# power_supply_switching.net
KiCad netlist of a schematic drawn in Altium Designer
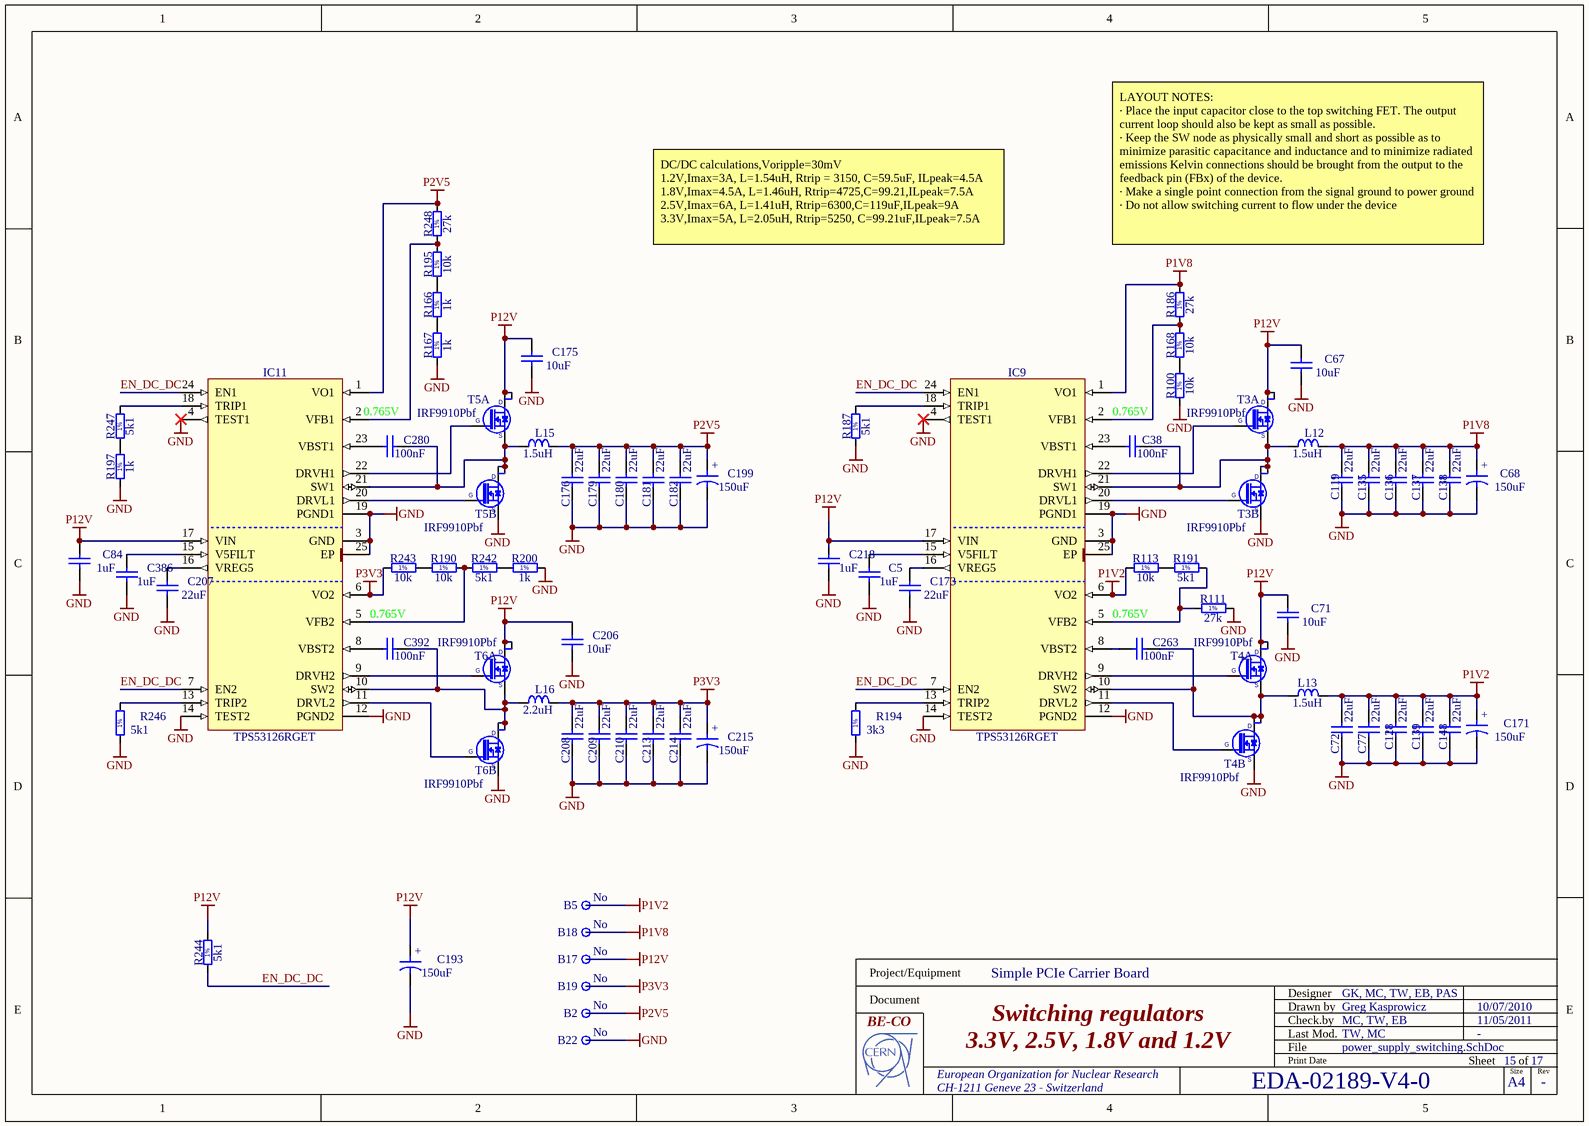
[diagram p0: power_supply_switching.SchDoc]

(export (version "E")
  (design (tool "Eeschema 10.0.6"))
  (components
    (comp (ref "B2")
      (value "Test Point")
      (footprint "VERO_20-2136")
      (description "Single Terminal Socket")
      (fields
        (field (name "PART NUMBER") "VERO_20-2136")
        (field (name "MOUNTED") "No")
        (field (name "MANUFACTURER") "VERO TECHNOLOGIES")
        (field (name "AUTHOR") "CERN DEM JLC")
      )
      (libsource (lib "Connectors") (part "Single Terminal Socket"))
    )
    (comp (ref "B5")
      (value "Test Point")
      (footprint "VERO_20-2136")
      (description "Single Terminal Socket")
      (fields
        (field (name "PART NUMBER") "VERO_20-2136")
        (field (name "MOUNTED") "No")
        (field (name "MANUFACTURER") "VERO TECHNOLOGIES")
        (field (name "AUTHOR") "CERN DEM JLC")
      )
      (libsource (lib "Connectors") (part "Single Terminal Socket"))
    )
    (comp (ref "B17")
      (value "Test Point")
      (footprint "VERO_20-2136")
      (description "Single Terminal Socket")
      (fields
        (field (name "PART NUMBER") "VERO_20-2136")
        (field (name "MOUNTED") "No")
        (field (name "MANUFACTURER") "VERO TECHNOLOGIES")
        (field (name "AUTHOR") "CERN DEM JLC")
      )
      (libsource (lib "Connectors") (part "Single Terminal Socket"))
    )
    (comp (ref "B18")
      (value "Test Point")
      (footprint "VERO_20-2136")
      (description "Single Terminal Socket")
      (fields
        (field (name "PART NUMBER") "VERO_20-2136")
        (field (name "MOUNTED") "No")
        (field (name "MANUFACTURER") "VERO TECHNOLOGIES")
        (field (name "AUTHOR") "CERN DEM JLC")
      )
      (libsource (lib "Connectors") (part "Single Terminal Socket"))
    )
    (comp (ref "B19")
      (value "Test Point")
      (footprint "VERO_20-2136")
      (description "Single Terminal Socket")
      (fields
        (field (name "PART NUMBER") "VERO_20-2136")
        (field (name "MOUNTED") "No")
        (field (name "MANUFACTURER") "VERO TECHNOLOGIES")
        (field (name "AUTHOR") "CERN DEM JLC")
      )
      (libsource (lib "Connectors") (part "Single Terminal Socket"))
    )
    (comp (ref "B22")
      (value "Test Point")
      (footprint "VERO_20-2136")
      (description "Single Terminal Socket")
      (fields
        (field (name "PART NUMBER") "VERO_20-2136")
        (field (name "MOUNTED") "No")
        (field (name "MANUFACTURER") "VERO TECHNOLOGIES")
        (field (name "AUTHOR") "CERN DEM JLC")
      )
      (libsource (lib "Connectors") (part "Single Terminal Socket"))
    )
    (comp (ref "C5")
      (value "1uF")
      (footprint "CAPC1608X87N")
      (description "Non-polarised capacitor")
      (fields
        (field (name "PART NUMBER") "CC0603_1UF_16V_10%_X7R")
        (field (name "VOLTAGE") "16V")
        (field (name "AUTHOR") "CERN DEM JLC")
      )
      (libsource (lib "Capacitors") (part "Capacitor - non polarized"))
    )
    (comp (ref "C38")
      (value "100nF")
      (footprint "CAPC1608X87N")
      (description "Non-polarised capacitor")
      (fields
        (field (name "PART NUMBER") "CC0603_100NF_50V_10%_X7R")
        (field (name "VOLTAGE") "50V")
        (field (name "AUTHOR") "CERN DEM JLC")
      )
      (libsource (lib "Capacitors") (part "Capacitor - non polarized"))
    )
    (comp (ref "C67")
      (value "10uF")
      (footprint "CAPC3225X270N")
      (description "Non-polarised capacitor")
      (fields
        (field (name "PART NUMBER") "CC1210_10UF_25V_10%_X7R")
        (field (name "VOLTAGE") "25V")
        (field (name "AUTHOR") "CERN DEM JLC")
      )
      (libsource (lib "Capacitors") (part "Capacitor - non polarized"))
    )
    (comp (ref "C68")
      (value "150uF")
      (footprint "CAPPR350-850X700")
      (description "Polarised capacitor")
      (fields
        (field (name "PART NUMBER") "CAER_150UF_6.3V_20%_SANYO_6SEQP150M")
        (field (name "VOLTAGE") "6.3V")
        (field (name "AUTHOR") "CERN DEM JLC")
      )
      (libsource (lib "Capacitors") (part "Capacitor - polarized"))
    )
    (comp (ref "C71")
      (value "10uF")
      (footprint "CAPC3225X270N")
      (description "Non-polarised capacitor")
      (fields
        (field (name "PART NUMBER") "CC1210_10UF_25V_10%_X7R")
        (field (name "VOLTAGE") "25V")
        (field (name "AUTHOR") "CERN DEM JLC")
      )
      (libsource (lib "Capacitors") (part "Capacitor - non polarized"))
    )
    (comp (ref "C72")
      (value "22uF")
      (footprint "CAPC3216X180N")
      (description "Non-polarised capacitor")
      (fields
        (field (name "PART NUMBER") "CC1206_22UF_10V_10%_X7R")
        (field (name "VOLTAGE") "10V")
        (field (name "AUTHOR") "CERN DEM JLC")
      )
      (libsource (lib "Capacitors") (part "Capacitor - non polarized"))
    )
    (comp (ref "C77")
      (value "22uF")
      (footprint "CAPC3216X180N")
      (description "Non-polarised capacitor")
      (fields
        (field (name "PART NUMBER") "CC1206_22UF_10V_10%_X7R")
        (field (name "VOLTAGE") "10V")
        (field (name "AUTHOR") "CERN DEM JLC")
      )
      (libsource (lib "Capacitors") (part "Capacitor - non polarized"))
    )
    (comp (ref "C84")
      (value "1uF")
      (footprint "CAPC1608X87N")
      (description "Non-polarised capacitor")
      (fields
        (field (name "PART NUMBER") "CC0603_1UF_16V_10%_X7R")
        (field (name "VOLTAGE") "16V")
        (field (name "AUTHOR") "CERN DEM JLC")
      )
      (libsource (lib "Capacitors") (part "Capacitor - non polarized"))
    )
    (comp (ref "C119")
      (value "22uF")
      (footprint "CAPC3216X180N")
      (description "Non-polarised capacitor")
      (fields
        (field (name "PART NUMBER") "CC1206_22UF_10V_10%_X7R")
        (field (name "VOLTAGE") "10V")
        (field (name "AUTHOR") "CERN DEM JLC")
      )
      (libsource (lib "Capacitors") (part "Capacitor - non polarized"))
    )
    (comp (ref "C128")
      (value "22uF")
      (footprint "CAPC3216X180N")
      (description "Non-polarised capacitor")
      (fields
        (field (name "PART NUMBER") "CC1206_22UF_10V_10%_X7R")
        (field (name "VOLTAGE") "10V")
        (field (name "AUTHOR") "CERN DEM JLC")
      )
      (libsource (lib "Capacitors") (part "Capacitor - non polarized"))
    )
    (comp (ref "C135")
      (value "22uF")
      (footprint "CAPC3216X180N")
      (description "Non-polarised capacitor")
      (fields
        (field (name "PART NUMBER") "CC1206_22UF_10V_10%_X7R")
        (field (name "VOLTAGE") "10V")
        (field (name "AUTHOR") "CERN DEM JLC")
      )
      (libsource (lib "Capacitors") (part "Capacitor - non polarized"))
    )
    (comp (ref "C136")
      (value "22uF")
      (footprint "CAPC3216X180N")
      (description "Non-polarised capacitor")
      (fields
        (field (name "PART NUMBER") "CC1206_22UF_10V_10%_X7R")
        (field (name "VOLTAGE") "10V")
        (field (name "AUTHOR") "CERN DEM JLC")
      )
      (libsource (lib "Capacitors") (part "Capacitor - non polarized"))
    )
    (comp (ref "C137")
      (value "22uF")
      (footprint "CAPC3216X180N")
      (description "Non-polarised capacitor")
      (fields
        (field (name "PART NUMBER") "CC1206_22UF_10V_10%_X7R")
        (field (name "VOLTAGE") "10V")
        (field (name "AUTHOR") "CERN DEM JLC")
      )
      (libsource (lib "Capacitors") (part "Capacitor - non polarized"))
    )
    (comp (ref "C138")
      (value "22uF")
      (footprint "CAPC3216X180N")
      (description "Non-polarised capacitor")
      (fields
        (field (name "PART NUMBER") "CC1206_22UF_10V_10%_X7R")
        (field (name "VOLTAGE") "10V")
        (field (name "AUTHOR") "CERN DEM JLC")
      )
      (libsource (lib "Capacitors") (part "Capacitor - non polarized"))
    )
    (comp (ref "C139")
      (value "22uF")
      (footprint "CAPC3216X180N")
      (description "Non-polarised capacitor")
      (fields
        (field (name "PART NUMBER") "CC1206_22UF_10V_10%_X7R")
        (field (name "VOLTAGE") "10V")
        (field (name "AUTHOR") "CERN DEM JLC")
      )
      (libsource (lib "Capacitors") (part "Capacitor - non polarized"))
    )
    (comp (ref "C148")
      (value "22uF")
      (footprint "CAPC3216X180N")
      (description "Non-polarised capacitor")
      (fields
        (field (name "PART NUMBER") "CC1206_22UF_10V_10%_X7R")
        (field (name "VOLTAGE") "10V")
        (field (name "AUTHOR") "CERN DEM JLC")
      )
      (libsource (lib "Capacitors") (part "Capacitor - non polarized"))
    )
    (comp (ref "C171")
      (value "150uF")
      (footprint "CAPPR350-850X700")
      (description "Polarised capacitor")
      (fields
        (field (name "PART NUMBER") "CAER_150UF_6.3V_20%_SANYO_6SEQP150M")
        (field (name "VOLTAGE") "6.3V")
        (field (name "AUTHOR") "CERN DEM JLC")
      )
      (libsource (lib "Capacitors") (part "Capacitor - polarized"))
    )
    (comp (ref "C173")
      (value "22uF")
      (footprint "CAPC3216X180N")
      (description "Non-polarised capacitor")
      (fields
        (field (name "PART NUMBER") "CC1206_22UF_10V_10%_X7R")
        (field (name "VOLTAGE") "10V")
        (field (name "AUTHOR") "CERN DEM JLC")
      )
      (libsource (lib "Capacitors") (part "Capacitor - non polarized"))
    )
    (comp (ref "C175")
      (value "10uF")
      (footprint "CAPC3225X270N")
      (description "Non-polarised capacitor")
      (fields
        (field (name "PART NUMBER") "CC1210_10UF_25V_10%_X7R")
        (field (name "VOLTAGE") "25V")
        (field (name "AUTHOR") "CERN DEM JLC")
      )
      (libsource (lib "Capacitors") (part "Capacitor - non polarized"))
    )
    (comp (ref "C176")
      (value "22uF")
      (footprint "CAPC3216X180N")
      (description "Non-polarised capacitor")
      (fields
        (field (name "PART NUMBER") "CC1206_22UF_10V_10%_X7R")
        (field (name "VOLTAGE") "10V")
        (field (name "AUTHOR") "CERN DEM JLC")
      )
      (libsource (lib "Capacitors") (part "Capacitor - non polarized"))
    )
    (comp (ref "C179")
      (value "22uF")
      (footprint "CAPC3216X180N")
      (description "Non-polarised capacitor")
      (fields
        (field (name "PART NUMBER") "CC1206_22UF_10V_10%_X7R")
        (field (name "VOLTAGE") "10V")
        (field (name "AUTHOR") "CERN DEM JLC")
      )
      (libsource (lib "Capacitors") (part "Capacitor - non polarized"))
    )
    (comp (ref "C180")
      (value "22uF")
      (footprint "CAPC3216X180N")
      (description "Non-polarised capacitor")
      (fields
        (field (name "PART NUMBER") "CC1206_22UF_10V_10%_X7R")
        (field (name "VOLTAGE") "10V")
        (field (name "AUTHOR") "CERN DEM JLC")
      )
      (libsource (lib "Capacitors") (part "Capacitor - non polarized"))
    )
    (comp (ref "C181")
      (value "22uF")
      (footprint "CAPC3216X180N")
      (description "Non-polarised capacitor")
      (fields
        (field (name "PART NUMBER") "CC1206_22UF_10V_10%_X7R")
        (field (name "VOLTAGE") "10V")
        (field (name "AUTHOR") "CERN DEM JLC")
      )
      (libsource (lib "Capacitors") (part "Capacitor - non polarized"))
    )
    (comp (ref "C182")
      (value "22uF")
      (footprint "CAPC3216X180N")
      (description "Non-polarised capacitor")
      (fields
        (field (name "PART NUMBER") "CC1206_22UF_10V_10%_X7R")
        (field (name "VOLTAGE") "10V")
        (field (name "AUTHOR") "CERN DEM JLC")
      )
      (libsource (lib "Capacitors") (part "Capacitor - non polarized"))
    )
    (comp (ref "C193")
      (value "150uF")
      (footprint "CAPPR500-1050X800")
      (description "Polarised capacitor")
      (fields
        (field (name "PART NUMBER") "CAER_150UF_16V_20%_SANYO_16SEQP150M")
        (field (name "VOLTAGE") "16V")
        (field (name "AUTHOR") "CERN DEM JLC")
      )
      (libsource (lib "Capacitors") (part "Capacitor - polarized"))
    )
    (comp (ref "C199")
      (value "150uF")
      (footprint "CAPPR350-850X700")
      (description "Polarised capacitor")
      (fields
        (field (name "PART NUMBER") "CAER_150UF_6.3V_20%_SANYO_6SEQP150M")
        (field (name "VOLTAGE") "6.3V")
        (field (name "AUTHOR") "CERN DEM JLC")
      )
      (libsource (lib "Capacitors") (part "Capacitor - polarized"))
    )
    (comp (ref "C206")
      (value "10uF")
      (footprint "CAPC3225X270N")
      (description "Non-polarised capacitor")
      (fields
        (field (name "PART NUMBER") "CC1210_10UF_25V_10%_X7R")
        (field (name "VOLTAGE") "25V")
        (field (name "AUTHOR") "CERN DEM JLC")
      )
      (libsource (lib "Capacitors") (part "Capacitor - non polarized"))
    )
    (comp (ref "C207")
      (value "22uF")
      (footprint "CAPC3216X180N")
      (description "Non-polarised capacitor")
      (fields
        (field (name "PART NUMBER") "CC1206_22UF_10V_10%_X7R")
        (field (name "VOLTAGE") "10V")
        (field (name "AUTHOR") "CERN DEM JLC")
      )
      (libsource (lib "Capacitors") (part "Capacitor - non polarized"))
    )
    (comp (ref "C208")
      (value "22uF")
      (footprint "CAPC3216X180N")
      (description "Non-polarised capacitor")
      (fields
        (field (name "PART NUMBER") "CC1206_22UF_10V_10%_X7R")
        (field (name "VOLTAGE") "10V")
        (field (name "AUTHOR") "CERN DEM JLC")
      )
      (libsource (lib "Capacitors") (part "Capacitor - non polarized"))
    )
    (comp (ref "C209")
      (value "22uF")
      (footprint "CAPC3216X180N")
      (description "Non-polarised capacitor")
      (fields
        (field (name "PART NUMBER") "CC1206_22UF_10V_10%_X7R")
        (field (name "VOLTAGE") "10V")
        (field (name "AUTHOR") "CERN DEM JLC")
      )
      (libsource (lib "Capacitors") (part "Capacitor - non polarized"))
    )
    (comp (ref "C210")
      (value "22uF")
      (footprint "CAPC3216X180N")
      (description "Non-polarised capacitor")
      (fields
        (field (name "PART NUMBER") "CC1206_22UF_10V_10%_X7R")
        (field (name "VOLTAGE") "10V")
        (field (name "AUTHOR") "CERN DEM JLC")
      )
      (libsource (lib "Capacitors") (part "Capacitor - non polarized"))
    )
    (comp (ref "C213")
      (value "22uF")
      (footprint "CAPC3216X180N")
      (description "Non-polarised capacitor")
      (fields
        (field (name "PART NUMBER") "CC1206_22UF_10V_10%_X7R")
        (field (name "VOLTAGE") "10V")
        (field (name "AUTHOR") "CERN DEM JLC")
      )
      (libsource (lib "Capacitors") (part "Capacitor - non polarized"))
    )
    (comp (ref "C214")
      (value "22uF")
      (footprint "CAPC3216X180N")
      (description "Non-polarised capacitor")
      (fields
        (field (name "PART NUMBER") "CC1206_22UF_10V_10%_X7R")
        (field (name "VOLTAGE") "10V")
        (field (name "AUTHOR") "CERN DEM JLC")
      )
      (libsource (lib "Capacitors") (part "Capacitor - non polarized"))
    )
    (comp (ref "C215")
      (value "150uF")
      (footprint "CAPPR350-850X700")
      (description "Polarised capacitor")
      (fields
        (field (name "PART NUMBER") "CAER_150UF_6.3V_20%_SANYO_6SEQP150M")
        (field (name "VOLTAGE") "6.3V")
        (field (name "AUTHOR") "CERN DEM JLC")
      )
      (libsource (lib "Capacitors") (part "Capacitor - polarized"))
    )
    (comp (ref "C218")
      (value "1uF")
      (footprint "CAPC1608X87N")
      (description "Non-polarised capacitor")
      (fields
        (field (name "PART NUMBER") "CC0603_1UF_16V_10%_X7R")
        (field (name "VOLTAGE") "16V")
        (field (name "AUTHOR") "CERN DEM JLC")
      )
      (libsource (lib "Capacitors") (part "Capacitor - non polarized"))
    )
    (comp (ref "C263")
      (value "100nF")
      (footprint "CAPC1608X87N")
      (description "Non-polarised capacitor")
      (fields
        (field (name "PART NUMBER") "CC0603_100NF_50V_10%_X7R")
        (field (name "VOLTAGE") "50V")
        (field (name "AUTHOR") "CERN DEM JLC")
      )
      (libsource (lib "Capacitors") (part "Capacitor - non polarized"))
    )
    (comp (ref "C280")
      (value "100nF")
      (footprint "CAPC1608X87N")
      (description "Non-polarised capacitor")
      (fields
        (field (name "PART NUMBER") "CC0603_100NF_50V_10%_X7R")
        (field (name "VOLTAGE") "50V")
        (field (name "AUTHOR") "CERN DEM JLC")
      )
      (libsource (lib "Capacitors") (part "Capacitor - non polarized"))
    )
    (comp (ref "C386")
      (value "1uF")
      (footprint "CAPC1608X87N")
      (description "Non-polarised capacitor")
      (fields
        (field (name "PART NUMBER") "CC0603_1UF_16V_10%_X7R")
        (field (name "VOLTAGE") "16V")
        (field (name "AUTHOR") "CERN DEM JLC")
      )
      (libsource (lib "Capacitors") (part "Capacitor - non polarized"))
    )
    (comp (ref "C392")
      (value "100nF")
      (footprint "CAPC1608X87N")
      (description "Non-polarised capacitor")
      (fields
        (field (name "PART NUMBER") "CC0603_100NF_50V_10%_X7R")
        (field (name "VOLTAGE") "50V")
        (field (name "AUTHOR") "CERN DEM JLC")
      )
      (libsource (lib "Capacitors") (part "Capacitor - non polarized"))
    )
    (comp (ref "IC9")
      (value "TPS53126RGET")
      (footprint "QFN50P400X400X100-25N-S255")
      (description "Dual Synchronous Step-Down Controller For Low Voltage Power Rails")
      (fields (field (name "MANUFACTURER") "TEXAS INSTRUMENTS") (field (name "AUTHOR") "CERN DEM JLC"))
      (libsource (lib "ICs And Semiconductors") (part "TPS53126RGET"))
    )
    (comp (ref "IC11")
      (value "TPS53126RGET")
      (footprint "QFN50P400X400X100-25N-S255")
      (description "Dual Synchronous Step-Down Controller For Low Voltage Power Rails")
      (fields (field (name "MANUFACTURER") "TEXAS INSTRUMENTS") (field (name "AUTHOR") "CERN DEM JLC"))
      (libsource (lib "ICs And Semiconductors") (part "TPS53126RGET"))
    )
    (comp (ref "L12")
      (value "1.5uH")
      (footprint "IND_BOURNS_SRR1260")
      (description "Inductor")
      (fields
        (field (name "PART NUMBER") "IND_1.5UH_30%_BOURNS_SRR1260")
        (field (name "POWER") "8.8A")
        (field (name "AUTHOR") "CERN DEM JLC")
      )
      (libsource (lib "Inductors & Transformers") (part "Inductor"))
    )
    (comp (ref "L13")
      (value "1.5uH")
      (footprint "IND_BOURNS_SRR1260")
      (description "Inductor")
      (fields
        (field (name "PART NUMBER") "IND_1.5UH_30%_BOURNS_SRR1260")
        (field (name "POWER") "8.8A")
        (field (name "AUTHOR") "CERN DEM JLC")
      )
      (libsource (lib "Inductors & Transformers") (part "Inductor"))
    )
    (comp (ref "L15")
      (value "1.5uH")
      (footprint "IND_BOURNS_SRR1260")
      (description "Inductor")
      (fields
        (field (name "PART NUMBER") "IND_1.5UH_30%_BOURNS_SRR1260")
        (field (name "POWER") "8.8A")
        (field (name "AUTHOR") "CERN DEM JLC")
      )
      (libsource (lib "Inductors & Transformers") (part "Inductor"))
    )
    (comp (ref "L16")
      (value "2.2uH")
      (footprint "IND_BOURNS_SRR1260")
      (description "Inductor")
      (fields
        (field (name "PART NUMBER") "IND_2.2UH_30%_BOURNS_SRR1260")
        (field (name "POWER") "8.2A")
        (field (name "AUTHOR") "CERN DEM JLC")
      )
      (libsource (lib "Inductors & Transformers") (part "Inductor"))
    )
    (comp (ref "R100")
      (value "10k")
      (footprint "RESC1608X55N")
      (description "Resistor - 1%")
      (fields
        (field (name "PART NUMBER") "R0603_10K_1%_0.1W_100PPM")
        (field (name "POWER") "0.1W")
        (field (name "AUTHOR") "CERN DEM JLC")
      )
      (libsource (lib "Resistors") (part "Resistor - 1%"))
    )
    (comp (ref "R111")
      (value "27k")
      (footprint "RESC1608X55N")
      (description "Resistor - 1%")
      (fields
        (field (name "PART NUMBER") "R0603_27K_1%_0.1W_100PPM")
        (field (name "POWER") "0.1W")
        (field (name "AUTHOR") "CERN DEM JLC")
      )
      (libsource (lib "Resistors") (part "Resistor - 1%"))
    )
    (comp (ref "R113")
      (value "10k")
      (footprint "RESC1608X55N")
      (description "Resistor - 1%")
      (fields
        (field (name "PART NUMBER") "R0603_10K_1%_0.1W_100PPM")
        (field (name "POWER") "0.1W")
        (field (name "AUTHOR") "CERN DEM JLC")
      )
      (libsource (lib "Resistors") (part "Resistor - 1%"))
    )
    (comp (ref "R166")
      (value "1k")
      (footprint "RESC1608X55N")
      (description "Resistor - 1%")
      (fields
        (field (name "PART NUMBER") "R0603_1K_1%_0.1W_100PPM")
        (field (name "POWER") "0.1W")
        (field (name "AUTHOR") "CERN DEM JLC")
      )
      (libsource (lib "Resistors") (part "Resistor - 1%"))
    )
    (comp (ref "R167")
      (value "1k")
      (footprint "RESC1608X55N")
      (description "Resistor - 1%")
      (fields
        (field (name "PART NUMBER") "R0603_1K_1%_0.1W_100PPM")
        (field (name "POWER") "0.1W")
        (field (name "AUTHOR") "CERN DEM JLC")
      )
      (libsource (lib "Resistors") (part "Resistor - 1%"))
    )
    (comp (ref "R168")
      (value "10k")
      (footprint "RESC1608X55N")
      (description "Resistor - 1%")
      (fields
        (field (name "PART NUMBER") "R0603_10K_1%_0.1W_100PPM")
        (field (name "POWER") "0.1W")
        (field (name "AUTHOR") "CERN DEM JLC")
      )
      (libsource (lib "Resistors") (part "Resistor - 1%"))
    )
    (comp (ref "R186")
      (value "27k")
      (footprint "RESC1608X55N")
      (description "Resistor - 1%")
      (fields
        (field (name "PART NUMBER") "R0603_27K_1%_0.1W_100PPM")
        (field (name "POWER") "0.1W")
        (field (name "AUTHOR") "CERN DEM JLC")
      )
      (libsource (lib "Resistors") (part "Resistor - 1%"))
    )
    (comp (ref "R187")
      (value "5k1")
      (footprint "RESC1608X55N")
      (description "Resistor - 1%")
      (fields
        (field (name "PART NUMBER") "R0603_5K1_1%_0.1W_100PPM")
        (field (name "POWER") "0.1W")
        (field (name "AUTHOR") "CERN DEM JLC")
      )
      (libsource (lib "Resistors") (part "Resistor - 1%"))
    )
    (comp (ref "R190")
      (value "10k")
      (footprint "RESC1608X55N")
      (description "Resistor - 1%")
      (fields
        (field (name "PART NUMBER") "R0603_10K_1%_0.1W_100PPM")
        (field (name "POWER") "0.1W")
        (field (name "AUTHOR") "CERN DEM JLC")
      )
      (libsource (lib "Resistors") (part "Resistor - 1%"))
    )
    (comp (ref "R191")
      (value "5k1")
      (footprint "RESC1608X55N")
      (description "Resistor - 1%")
      (fields
        (field (name "PART NUMBER") "R0603_5K1_1%_0.1W_100PPM")
        (field (name "POWER") "0.1W")
        (field (name "AUTHOR") "CERN DEM JLC")
      )
      (libsource (lib "Resistors") (part "Resistor - 1%"))
    )
    (comp (ref "R194")
      (value "3k3")
      (footprint "RESC1608X55N")
      (description "Resistor - 1%")
      (fields
        (field (name "PART NUMBER") "R0603_3K3_1%_0.1W_100PPM")
        (field (name "POWER") "0.1W")
        (field (name "AUTHOR") "CERN DEM JLC")
      )
      (libsource (lib "Resistors") (part "Resistor - 1%"))
    )
    (comp (ref "R195")
      (value "10k")
      (footprint "RESC1608X55N")
      (description "Resistor - 1%")
      (fields
        (field (name "PART NUMBER") "R0603_10K_1%_0.1W_100PPM")
        (field (name "POWER") "0.1W")
        (field (name "AUTHOR") "CERN DEM JLC")
      )
      (libsource (lib "Resistors") (part "Resistor - 1%"))
    )
    (comp (ref "R197")
      (value "1k")
      (footprint "RESC1608X55N")
      (description "Resistor - 1%")
      (fields
        (field (name "PART NUMBER") "R0603_1K_1%_0.1W_100PPM")
        (field (name "POWER") "0.1W")
        (field (name "AUTHOR") "CERN DEM JLC")
      )
      (libsource (lib "Resistors") (part "Resistor - 1%"))
    )
    (comp (ref "R200")
      (value "1k")
      (footprint "RESC1608X55N")
      (description "Resistor - 1%")
      (fields
        (field (name "PART NUMBER") "R0603_1K_1%_0.1W_100PPM")
        (field (name "POWER") "0.1W")
        (field (name "AUTHOR") "CERN DEM JLC")
      )
      (libsource (lib "Resistors") (part "Resistor - 1%"))
    )
    (comp (ref "R242")
      (value "5k1")
      (footprint "RESC1608X55N")
      (description "Resistor - 1%")
      (fields
        (field (name "PART NUMBER") "R0603_5K1_1%_0.1W_100PPM")
        (field (name "POWER") "0.1W")
        (field (name "AUTHOR") "CERN DEM JLC")
      )
      (libsource (lib "Resistors") (part "Resistor - 1%"))
    )
    (comp (ref "R243")
      (value "10k")
      (footprint "RESC1608X55N")
      (description "Resistor - 1%")
      (fields
        (field (name "PART NUMBER") "R0603_10K_1%_0.1W_100PPM")
        (field (name "POWER") "0.1W")
        (field (name "AUTHOR") "CERN DEM JLC")
      )
      (libsource (lib "Resistors") (part "Resistor - 1%"))
    )
    (comp (ref "R244")
      (value "5k1")
      (footprint "RESC1608X55N")
      (description "Resistor - 1%")
      (fields
        (field (name "PART NUMBER") "R0603_5K1_1%_0.1W_100PPM")
        (field (name "POWER") "0.1W")
        (field (name "AUTHOR") "CERN DEM JLC")
      )
      (libsource (lib "Resistors") (part "Resistor - 1%"))
    )
    (comp (ref "R246")
      (value "5k1")
      (footprint "RESC1608X55N")
      (description "Resistor - 1%")
      (fields
        (field (name "PART NUMBER") "R0603_5K1_1%_0.1W_100PPM")
        (field (name "POWER") "0.1W")
        (field (name "AUTHOR") "CERN DEM JLC")
      )
      (libsource (lib "Resistors") (part "Resistor - 1%"))
    )
    (comp (ref "R247")
      (value "5k1")
      (footprint "RESC1608X55N")
      (description "Resistor - 1%")
      (fields
        (field (name "PART NUMBER") "R0603_5K1_1%_0.1W_100PPM")
        (field (name "POWER") "0.1W")
        (field (name "AUTHOR") "CERN DEM JLC")
      )
      (libsource (lib "Resistors") (part "Resistor - 1%"))
    )
    (comp (ref "R248")
      (value "27k")
      (footprint "RESC1608X55N")
      (description "Resistor - 1%")
      (fields
        (field (name "PART NUMBER") "R0603_27K_1%_0.1W_100PPM")
        (field (name "POWER") "0.1W")
        (field (name "AUTHOR") "CERN DEM JLC")
      )
      (libsource (lib "Resistors") (part "Resistor - 1%"))
    )
    (comp (ref "T3")
      (value "IRF9910Pbf")
      (footprint "SOIC127P600X175-8N")
      (description "Dual SO-8 MOSFET For POL Cconverter")
      (fields (field (name "MANUFACTURER") "INTERNATIONAL RECTIFIER") (field (name "AUTHOR") "CERN DEM JLC"))
      (libsource (lib "ICs And Semiconductors") (part "IRF9910"))
    )
    (comp (ref "T4")
      (value "IRF9910Pbf")
      (footprint "SOIC127P600X175-8N")
      (description "Dual SO-8 MOSFET For POL Cconverter")
      (fields (field (name "MANUFACTURER") "INTERNATIONAL RECTIFIER") (field (name "AUTHOR") "CERN DEM JLC"))
      (libsource (lib "ICs And Semiconductors") (part "IRF9910"))
    )
    (comp (ref "T5")
      (value "IRF9910Pbf")
      (footprint "SOIC127P600X175-8N")
      (description "Dual SO-8 MOSFET For POL Cconverter")
      (fields (field (name "MANUFACTURER") "INTERNATIONAL RECTIFIER") (field (name "AUTHOR") "CERN DEM JLC"))
      (libsource (lib "ICs And Semiconductors") (part "IRF9910"))
    )
    (comp (ref "T6")
      (value "IRF9910Pbf")
      (footprint "SOIC127P600X175-8N")
      (description "Dual SO-8 MOSFET For POL Cconverter")
      (fields (field (name "MANUFACTURER") "INTERNATIONAL RECTIFIER") (field (name "AUTHOR") "CERN DEM JLC"))
      (libsource (lib "ICs And Semiconductors") (part "IRF9910"))
    )
  )
  (nets
    (net (code "1") (name "/EN_DC_DC") (class "Default")
      (node (ref "IC11") (pin "24") (pinfunction "EN1_24") (pintype "input"))
      (node (ref "IC11") (pin "7") (pinfunction "EN2_7") (pintype "input"))
      (node (ref "IC9") (pin "24") (pinfunction "EN1_24") (pintype "input"))
      (node (ref "IC9") (pin "7") (pinfunction "EN2_7") (pintype "input"))
      (node (ref "R244") (pin "1") (pinfunction "1_1") (pintype "passive"))
    )
    (net (code "2") (name "GND") (class "Default")
      (node (ref "B22") (pin "1") (pinfunction "1_1") (pintype "bidirectional"))
      (node (ref "C119") (pin "1") (pinfunction "1_1") (pintype "passive"))
      (node (ref "C128") (pin "1") (pinfunction "1_1") (pintype "passive"))
      (node (ref "C135") (pin "1") (pinfunction "1_1") (pintype "passive"))
      (node (ref "C136") (pin "1") (pinfunction "1_1") (pintype "passive"))
      (node (ref "C137") (pin "1") (pinfunction "1_1") (pintype "passive"))
      (node (ref "C138") (pin "1") (pinfunction "1_1") (pintype "passive"))
      (node (ref "C139") (pin "1") (pinfunction "1_1") (pintype "passive"))
      (node (ref "C148") (pin "1") (pinfunction "1_1") (pintype "passive"))
      (node (ref "C171") (pin "2") (pinfunction "2_2") (pintype "passive"))
      (node (ref "C173") (pin "1") (pinfunction "1_1") (pintype "passive"))
      (node (ref "C175") (pin "2") (pinfunction "2_2") (pintype "passive"))
      (node (ref "C176") (pin "1") (pinfunction "1_1") (pintype "passive"))
      (node (ref "C179") (pin "1") (pinfunction "1_1") (pintype "passive"))
      (node (ref "C180") (pin "1") (pinfunction "1_1") (pintype "passive"))
      (node (ref "C181") (pin "1") (pinfunction "1_1") (pintype "passive"))
      (node (ref "C182") (pin "1") (pinfunction "1_1") (pintype "passive"))
      (node (ref "C193") (pin "2") (pinfunction "2_2") (pintype "passive"))
      (node (ref "C199") (pin "2") (pinfunction "2_2") (pintype "passive"))
      (node (ref "C206") (pin "2") (pinfunction "2_2") (pintype "passive"))
      (node (ref "C207") (pin "1") (pinfunction "1_1") (pintype "passive"))
      (node (ref "C208") (pin "1") (pinfunction "1_1") (pintype "passive"))
      (node (ref "C209") (pin "1") (pinfunction "1_1") (pintype "passive"))
      (node (ref "C210") (pin "1") (pinfunction "1_1") (pintype "passive"))
      (node (ref "C213") (pin "1") (pinfunction "1_1") (pintype "passive"))
      (node (ref "C214") (pin "1") (pinfunction "1_1") (pintype "passive"))
      (node (ref "C215") (pin "2") (pinfunction "2_2") (pintype "passive"))
      (node (ref "C218") (pin "1") (pinfunction "1_1") (pintype "passive"))
      (node (ref "C386") (pin "1") (pinfunction "1_1") (pintype "passive"))
      (node (ref "C5") (pin "1") (pinfunction "1_1") (pintype "passive"))
      (node (ref "C67") (pin "2") (pinfunction "2_2") (pintype "passive"))
      (node (ref "C68") (pin "2") (pinfunction "2_2") (pintype "passive"))
      (node (ref "C71") (pin "2") (pinfunction "2_2") (pintype "passive"))
      (node (ref "C72") (pin "1") (pinfunction "1_1") (pintype "passive"))
      (node (ref "C77") (pin "1") (pinfunction "1_1") (pintype "passive"))
      (node (ref "C84") (pin "2") (pinfunction "2_2") (pintype "passive"))
      (node (ref "IC11") (pin "12") (pinfunction "PGND2_12") (pintype "power_in"))
      (node (ref "IC11") (pin "14") (pinfunction "TEST2_14") (pintype "input"))
      (node (ref "IC11") (pin "19") (pinfunction "PGND1_19") (pintype "power_in"))
      (node (ref "IC11") (pin "25") (pinfunction "EP_25") (pintype "power_in"))
      (node (ref "IC11") (pin "3") (pinfunction "GND_3") (pintype "power_in"))
      (node (ref "IC11") (pin "4") (pinfunction "TEST1_4") (pintype "output"))
      (node (ref "IC9") (pin "12") (pinfunction "PGND2_12") (pintype "power_in"))
      (node (ref "IC9") (pin "14") (pinfunction "TEST2_14") (pintype "input"))
      (node (ref "IC9") (pin "19") (pinfunction "PGND1_19") (pintype "power_in"))
      (node (ref "IC9") (pin "25") (pinfunction "EP_25") (pintype "power_in"))
      (node (ref "IC9") (pin "3") (pinfunction "GND_3") (pintype "power_in"))
      (node (ref "IC9") (pin "4") (pinfunction "TEST1_4") (pintype "output"))
      (node (ref "R100") (pin "1") (pinfunction "1_1") (pintype "passive"))
      (node (ref "R111") (pin "2") (pinfunction "2_2") (pintype "passive"))
      (node (ref "R167") (pin "1") (pinfunction "1_1") (pintype "passive"))
      (node (ref "R187") (pin "1") (pinfunction "1_1") (pintype "passive"))
      (node (ref "R194") (pin "1") (pinfunction "1_1") (pintype "passive"))
      (node (ref "R197") (pin "1") (pinfunction "1_1") (pintype "passive"))
      (node (ref "R200") (pin "2") (pinfunction "2_2") (pintype "passive"))
      (node (ref "R246") (pin "1") (pinfunction "1_1") (pintype "passive"))
      (node (ref "T3") (pin "1") (pinfunction "S_1") (pintype "passive"))
      (node (ref "T4") (pin "1") (pinfunction "S_1") (pintype "passive"))
      (node (ref "T5") (pin "1") (pinfunction "S_1") (pintype "passive"))
      (node (ref "T6") (pin "1") (pinfunction "S_1") (pintype "passive"))
    )
    (net (code "3") (name "Net-(IC9-DRVH1)") (class "Default")
      (node (ref "IC9") (pin "22") (pinfunction "DRVH1_22") (pintype "output"))
      (node (ref "T3") (pin "4") (pinfunction "G_4") (pintype "passive"))
    )
    (net (code "4") (name "Net-(IC9-DRVH2)") (class "Default")
      (node (ref "IC9") (pin "9") (pinfunction "DRVH2_9") (pintype "output"))
      (node (ref "T4") (pin "4") (pinfunction "G_4") (pintype "passive"))
    )
    (net (code "5") (name "Net-(IC9-DRVL1)") (class "Default")
      (node (ref "IC9") (pin "20") (pinfunction "DRVL1_20") (pintype "output"))
      (node (ref "T3") (pin "2") (pinfunction "G_2") (pintype "passive"))
    )
    (net (code "6") (name "Net-(IC9-DRVL2)") (class "Default")
      (node (ref "IC9") (pin "11") (pinfunction "DRVL2_11") (pintype "output"))
      (node (ref "T4") (pin "2") (pinfunction "G_2") (pintype "passive"))
    )
    (net (code "7") (name "Net-(IC9-SW1)") (class "Default")
      (node (ref "C38") (pin "1") (pinfunction "1_1") (pintype "passive"))
      (node (ref "IC9") (pin "21") (pinfunction "SW1_21") (pintype "bidirectional"))
      (node (ref "L12") (pin "1") (pinfunction "1_1") (pintype "passive"))
      (node (ref "T3") (pin "3") (pinfunction "S_3") (pintype "passive"))
      (node (ref "T3") (pin "7") (pinfunction "D_7") (pintype "passive"))
      (node (ref "T3") (pin "8") (pinfunction "D_8") (pintype "passive"))
    )
    (net (code "8") (name "Net-(IC9-SW2)") (class "Default")
      (node (ref "C263") (pin "1") (pinfunction "1_1") (pintype "passive"))
      (node (ref "IC9") (pin "10") (pinfunction "SW2_10") (pintype "bidirectional"))
      (node (ref "L13") (pin "1") (pinfunction "1_1") (pintype "passive"))
      (node (ref "T4") (pin "3") (pinfunction "S_3") (pintype "passive"))
      (node (ref "T4") (pin "7") (pinfunction "D_7") (pintype "passive"))
      (node (ref "T4") (pin "8") (pinfunction "D_8") (pintype "passive"))
    )
    (net (code "9") (name "Net-(IC9-TRIP1)") (class "Default")
      (node (ref "IC9") (pin "18") (pinfunction "TRIP1_18") (pintype "input"))
      (node (ref "R187") (pin "2") (pinfunction "2_2") (pintype "passive"))
    )
    (net (code "10") (name "Net-(IC9-TRIP2)") (class "Default")
      (node (ref "IC9") (pin "13") (pinfunction "TRIP2_13") (pintype "input"))
      (node (ref "R194") (pin "2") (pinfunction "2_2") (pintype "passive"))
    )
    (net (code "11") (name "Net-(IC9-V5FILT)") (class "Default")
      (node (ref "C5") (pin "2") (pinfunction "2_2") (pintype "passive"))
      (node (ref "IC9") (pin "15") (pinfunction "V5FILT_15") (pintype "input"))
    )
    (net (code "12") (name "Net-(IC9-VBST1)") (class "Default")
      (node (ref "C38") (pin "2") (pinfunction "2_2") (pintype "passive"))
      (node (ref "IC9") (pin "23") (pinfunction "VBST1_23") (pintype "input"))
    )
    (net (code "13") (name "Net-(IC9-VBST2)") (class "Default")
      (node (ref "C263") (pin "2") (pinfunction "2_2") (pintype "passive"))
      (node (ref "IC9") (pin "8") (pinfunction "VBST2_8") (pintype "input"))
    )
    (net (code "14") (name "Net-(IC9-VFB1)") (class "Default")
      (node (ref "IC9") (pin "2") (pinfunction "VFB1_2") (pintype "input"))
      (node (ref "R168") (pin "2") (pinfunction "2_2") (pintype "passive"))
      (node (ref "R186") (pin "1") (pinfunction "1_1") (pintype "passive"))
    )
    (net (code "15") (name "Net-(IC9-VFB2)") (class "Default")
      (node (ref "IC9") (pin "5") (pinfunction "VFB2_5") (pintype "input"))
      (node (ref "R111") (pin "1") (pinfunction "1_1") (pintype "passive"))
      (node (ref "R191") (pin "2") (pinfunction "2_2") (pintype "passive"))
    )
    (net (code "16") (name "Net-(IC9-VREG5)") (class "Default")
      (node (ref "C173") (pin "2") (pinfunction "2_2") (pintype "passive"))
      (node (ref "IC9") (pin "16") (pinfunction "VREG5_16") (pintype "output"))
    )
    (net (code "17") (name "Net-(IC11-DRVH1)") (class "Default")
      (node (ref "IC11") (pin "22") (pinfunction "DRVH1_22") (pintype "output"))
      (node (ref "T5") (pin "4") (pinfunction "G_4") (pintype "passive"))
    )
    (net (code "18") (name "Net-(IC11-DRVH2)") (class "Default")
      (node (ref "IC11") (pin "9") (pinfunction "DRVH2_9") (pintype "output"))
      (node (ref "T6") (pin "4") (pinfunction "G_4") (pintype "passive"))
    )
    (net (code "19") (name "Net-(IC11-DRVL1)") (class "Default")
      (node (ref "IC11") (pin "20") (pinfunction "DRVL1_20") (pintype "output"))
      (node (ref "T5") (pin "2") (pinfunction "G_2") (pintype "passive"))
    )
    (net (code "20") (name "Net-(IC11-DRVL2)") (class "Default")
      (node (ref "IC11") (pin "11") (pinfunction "DRVL2_11") (pintype "output"))
      (node (ref "T6") (pin "2") (pinfunction "G_2") (pintype "passive"))
    )
    (net (code "21") (name "Net-(IC11-SW1)") (class "Default")
      (node (ref "C280") (pin "1") (pinfunction "1_1") (pintype "passive"))
      (node (ref "IC11") (pin "21") (pinfunction "SW1_21") (pintype "bidirectional"))
      (node (ref "L15") (pin "1") (pinfunction "1_1") (pintype "passive"))
      (node (ref "T5") (pin "3") (pinfunction "S_3") (pintype "passive"))
      (node (ref "T5") (pin "7") (pinfunction "D_7") (pintype "passive"))
      (node (ref "T5") (pin "8") (pinfunction "D_8") (pintype "passive"))
    )
    (net (code "22") (name "Net-(IC11-SW2)") (class "Default")
      (node (ref "C392") (pin "1") (pinfunction "1_1") (pintype "passive"))
      (node (ref "IC11") (pin "10") (pinfunction "SW2_10") (pintype "bidirectional"))
      (node (ref "L16") (pin "1") (pinfunction "1_1") (pintype "passive"))
      (node (ref "T6") (pin "3") (pinfunction "S_3") (pintype "passive"))
      (node (ref "T6") (pin "7") (pinfunction "D_7") (pintype "passive"))
      (node (ref "T6") (pin "8") (pinfunction "D_8") (pintype "passive"))
    )
    (net (code "23") (name "Net-(IC11-TRIP1)") (class "Default")
      (node (ref "IC11") (pin "18") (pinfunction "TRIP1_18") (pintype "input"))
      (node (ref "R247") (pin "2") (pinfunction "2_2") (pintype "passive"))
    )
    (net (code "24") (name "Net-(IC11-TRIP2)") (class "Default")
      (node (ref "IC11") (pin "13") (pinfunction "TRIP2_13") (pintype "input"))
      (node (ref "R246") (pin "2") (pinfunction "2_2") (pintype "passive"))
    )
    (net (code "25") (name "Net-(IC11-V5FILT)") (class "Default")
      (node (ref "C386") (pin "2") (pinfunction "2_2") (pintype "passive"))
      (node (ref "IC11") (pin "15") (pinfunction "V5FILT_15") (pintype "input"))
    )
    (net (code "26") (name "Net-(IC11-VBST1)") (class "Default")
      (node (ref "C280") (pin "2") (pinfunction "2_2") (pintype "passive"))
      (node (ref "IC11") (pin "23") (pinfunction "VBST1_23") (pintype "input"))
    )
    (net (code "27") (name "Net-(IC11-VBST2)") (class "Default")
      (node (ref "C392") (pin "2") (pinfunction "2_2") (pintype "passive"))
      (node (ref "IC11") (pin "8") (pinfunction "VBST2_8") (pintype "input"))
    )
    (net (code "28") (name "Net-(IC11-VFB1)") (class "Default")
      (node (ref "IC11") (pin "2") (pinfunction "VFB1_2") (pintype "input"))
      (node (ref "R195") (pin "2") (pinfunction "2_2") (pintype "passive"))
      (node (ref "R248") (pin "1") (pinfunction "1_1") (pintype "passive"))
    )
    (net (code "29") (name "Net-(IC11-VFB2)") (class "Default")
      (node (ref "IC11") (pin "5") (pinfunction "VFB2_5") (pintype "input"))
      (node (ref "R190") (pin "2") (pinfunction "2_2") (pintype "passive"))
      (node (ref "R242") (pin "1") (pinfunction "1_1") (pintype "passive"))
    )
    (net (code "30") (name "Net-(IC11-VREG5)") (class "Default")
      (node (ref "C207") (pin "2") (pinfunction "2_2") (pintype "passive"))
      (node (ref "IC11") (pin "16") (pinfunction "VREG5_16") (pintype "output"))
    )
    (net (code "31") (name "Net-(R100-Pad2)") (class "Default")
      (node (ref "R100") (pin "2") (pinfunction "2_2") (pintype "passive"))
      (node (ref "R168") (pin "1") (pinfunction "1_1") (pintype "passive"))
    )
    (net (code "32") (name "Net-(R113-Pad2)") (class "Default")
      (node (ref "R113") (pin "2") (pinfunction "2_2") (pintype "passive"))
      (node (ref "R191") (pin "1") (pinfunction "1_1") (pintype "passive"))
    )
    (net (code "33") (name "Net-(R166-Pad1)") (class "Default")
      (node (ref "R166") (pin "1") (pinfunction "1_1") (pintype "passive"))
      (node (ref "R167") (pin "2") (pinfunction "2_2") (pintype "passive"))
    )
    (net (code "34") (name "Net-(R166-Pad2)") (class "Default")
      (node (ref "R166") (pin "2") (pinfunction "2_2") (pintype "passive"))
      (node (ref "R195") (pin "1") (pinfunction "1_1") (pintype "passive"))
    )
    (net (code "35") (name "Net-(R190-Pad1)") (class "Default")
      (node (ref "R190") (pin "1") (pinfunction "1_1") (pintype "passive"))
      (node (ref "R243") (pin "2") (pinfunction "2_2") (pintype "passive"))
    )
    (net (code "36") (name "Net-(R197-Pad2)") (class "Default")
      (node (ref "R197") (pin "2") (pinfunction "2_2") (pintype "passive"))
      (node (ref "R247") (pin "1") (pinfunction "1_1") (pintype "passive"))
    )
    (net (code "37") (name "Net-(R200-Pad1)") (class "Default")
      (node (ref "R200") (pin "1") (pinfunction "1_1") (pintype "passive"))
      (node (ref "R242") (pin "2") (pinfunction "2_2") (pintype "passive"))
    )
    (net (code "38") (name "P1V2") (class "Default")
      (node (ref "B5") (pin "1") (pinfunction "1_1") (pintype "bidirectional"))
      (node (ref "C128") (pin "2") (pinfunction "2_2") (pintype "passive"))
      (node (ref "C139") (pin "2") (pinfunction "2_2") (pintype "passive"))
      (node (ref "C148") (pin "2") (pinfunction "2_2") (pintype "passive"))
      (node (ref "C171") (pin "1") (pinfunction "1_1") (pintype "passive"))
      (node (ref "C72") (pin "2") (pinfunction "2_2") (pintype "passive"))
      (node (ref "C77") (pin "2") (pinfunction "2_2") (pintype "passive"))
      (node (ref "IC9") (pin "6") (pinfunction "VO2_6") (pintype "input"))
      (node (ref "L13") (pin "2") (pinfunction "2_2") (pintype "passive"))
      (node (ref "R113") (pin "1") (pinfunction "1_1") (pintype "passive"))
    )
    (net (code "39") (name "P1V8") (class "Default")
      (node (ref "B18") (pin "1") (pinfunction "1_1") (pintype "bidirectional"))
      (node (ref "C119") (pin "2") (pinfunction "2_2") (pintype "passive"))
      (node (ref "C135") (pin "2") (pinfunction "2_2") (pintype "passive"))
      (node (ref "C136") (pin "2") (pinfunction "2_2") (pintype "passive"))
      (node (ref "C137") (pin "2") (pinfunction "2_2") (pintype "passive"))
      (node (ref "C138") (pin "2") (pinfunction "2_2") (pintype "passive"))
      (node (ref "C68") (pin "1") (pinfunction "1_1") (pintype "passive"))
      (node (ref "IC9") (pin "1") (pinfunction "VO1_1") (pintype "input"))
      (node (ref "L12") (pin "2") (pinfunction "2_2") (pintype "passive"))
      (node (ref "R186") (pin "2") (pinfunction "2_2") (pintype "passive"))
    )
    (net (code "40") (name "P2V5") (class "Default")
      (node (ref "B2") (pin "1") (pinfunction "1_1") (pintype "bidirectional"))
      (node (ref "C176") (pin "2") (pinfunction "2_2") (pintype "passive"))
      (node (ref "C179") (pin "2") (pinfunction "2_2") (pintype "passive"))
      (node (ref "C180") (pin "2") (pinfunction "2_2") (pintype "passive"))
      (node (ref "C181") (pin "2") (pinfunction "2_2") (pintype "passive"))
      (node (ref "C182") (pin "2") (pinfunction "2_2") (pintype "passive"))
      (node (ref "C199") (pin "1") (pinfunction "1_1") (pintype "passive"))
      (node (ref "IC11") (pin "1") (pinfunction "VO1_1") (pintype "input"))
      (node (ref "L15") (pin "2") (pinfunction "2_2") (pintype "passive"))
      (node (ref "R248") (pin "2") (pinfunction "2_2") (pintype "passive"))
    )
    (net (code "41") (name "P3V3") (class "Default")
      (node (ref "B19") (pin "1") (pinfunction "1_1") (pintype "bidirectional"))
      (node (ref "C208") (pin "2") (pinfunction "2_2") (pintype "passive"))
      (node (ref "C209") (pin "2") (pinfunction "2_2") (pintype "passive"))
      (node (ref "C210") (pin "2") (pinfunction "2_2") (pintype "passive"))
      (node (ref "C213") (pin "2") (pinfunction "2_2") (pintype "passive"))
      (node (ref "C214") (pin "2") (pinfunction "2_2") (pintype "passive"))
      (node (ref "C215") (pin "1") (pinfunction "1_1") (pintype "passive"))
      (node (ref "IC11") (pin "6") (pinfunction "VO2_6") (pintype "input"))
      (node (ref "L16") (pin "2") (pinfunction "2_2") (pintype "passive"))
      (node (ref "R243") (pin "1") (pinfunction "1_1") (pintype "passive"))
    )
    (net (code "42") (name "P12V") (class "Default")
      (node (ref "B17") (pin "1") (pinfunction "1_1") (pintype "bidirectional"))
      (node (ref "C175") (pin "1") (pinfunction "1_1") (pintype "passive"))
      (node (ref "C193") (pin "1") (pinfunction "1_1") (pintype "passive"))
      (node (ref "C206") (pin "1") (pinfunction "1_1") (pintype "passive"))
      (node (ref "C218") (pin "2") (pinfunction "2_2") (pintype "passive"))
      (node (ref "C67") (pin "1") (pinfunction "1_1") (pintype "passive"))
      (node (ref "C71") (pin "1") (pinfunction "1_1") (pintype "passive"))
      (node (ref "C84") (pin "1") (pinfunction "1_1") (pintype "passive"))
      (node (ref "IC11") (pin "17") (pinfunction "VIN_17") (pintype "input"))
      (node (ref "IC9") (pin "17") (pinfunction "VIN_17") (pintype "input"))
      (node (ref "R244") (pin "2") (pinfunction "2_2") (pintype "passive"))
      (node (ref "T3") (pin "5") (pinfunction "D_5") (pintype "passive"))
      (node (ref "T3") (pin "6") (pinfunction "D_6") (pintype "passive"))
      (node (ref "T4") (pin "5") (pinfunction "D_5") (pintype "passive"))
      (node (ref "T4") (pin "6") (pinfunction "D_6") (pintype "passive"))
      (node (ref "T5") (pin "5") (pinfunction "D_5") (pintype "passive"))
      (node (ref "T5") (pin "6") (pinfunction "D_6") (pintype "passive"))
      (node (ref "T6") (pin "5") (pinfunction "D_5") (pintype "passive"))
      (node (ref "T6") (pin "6") (pinfunction "D_6") (pintype "passive"))
    )
  )
)
